# SX126xMB2xAS_e588v01a.net
KiCad netlist of a schematic drawn in Altium Designer
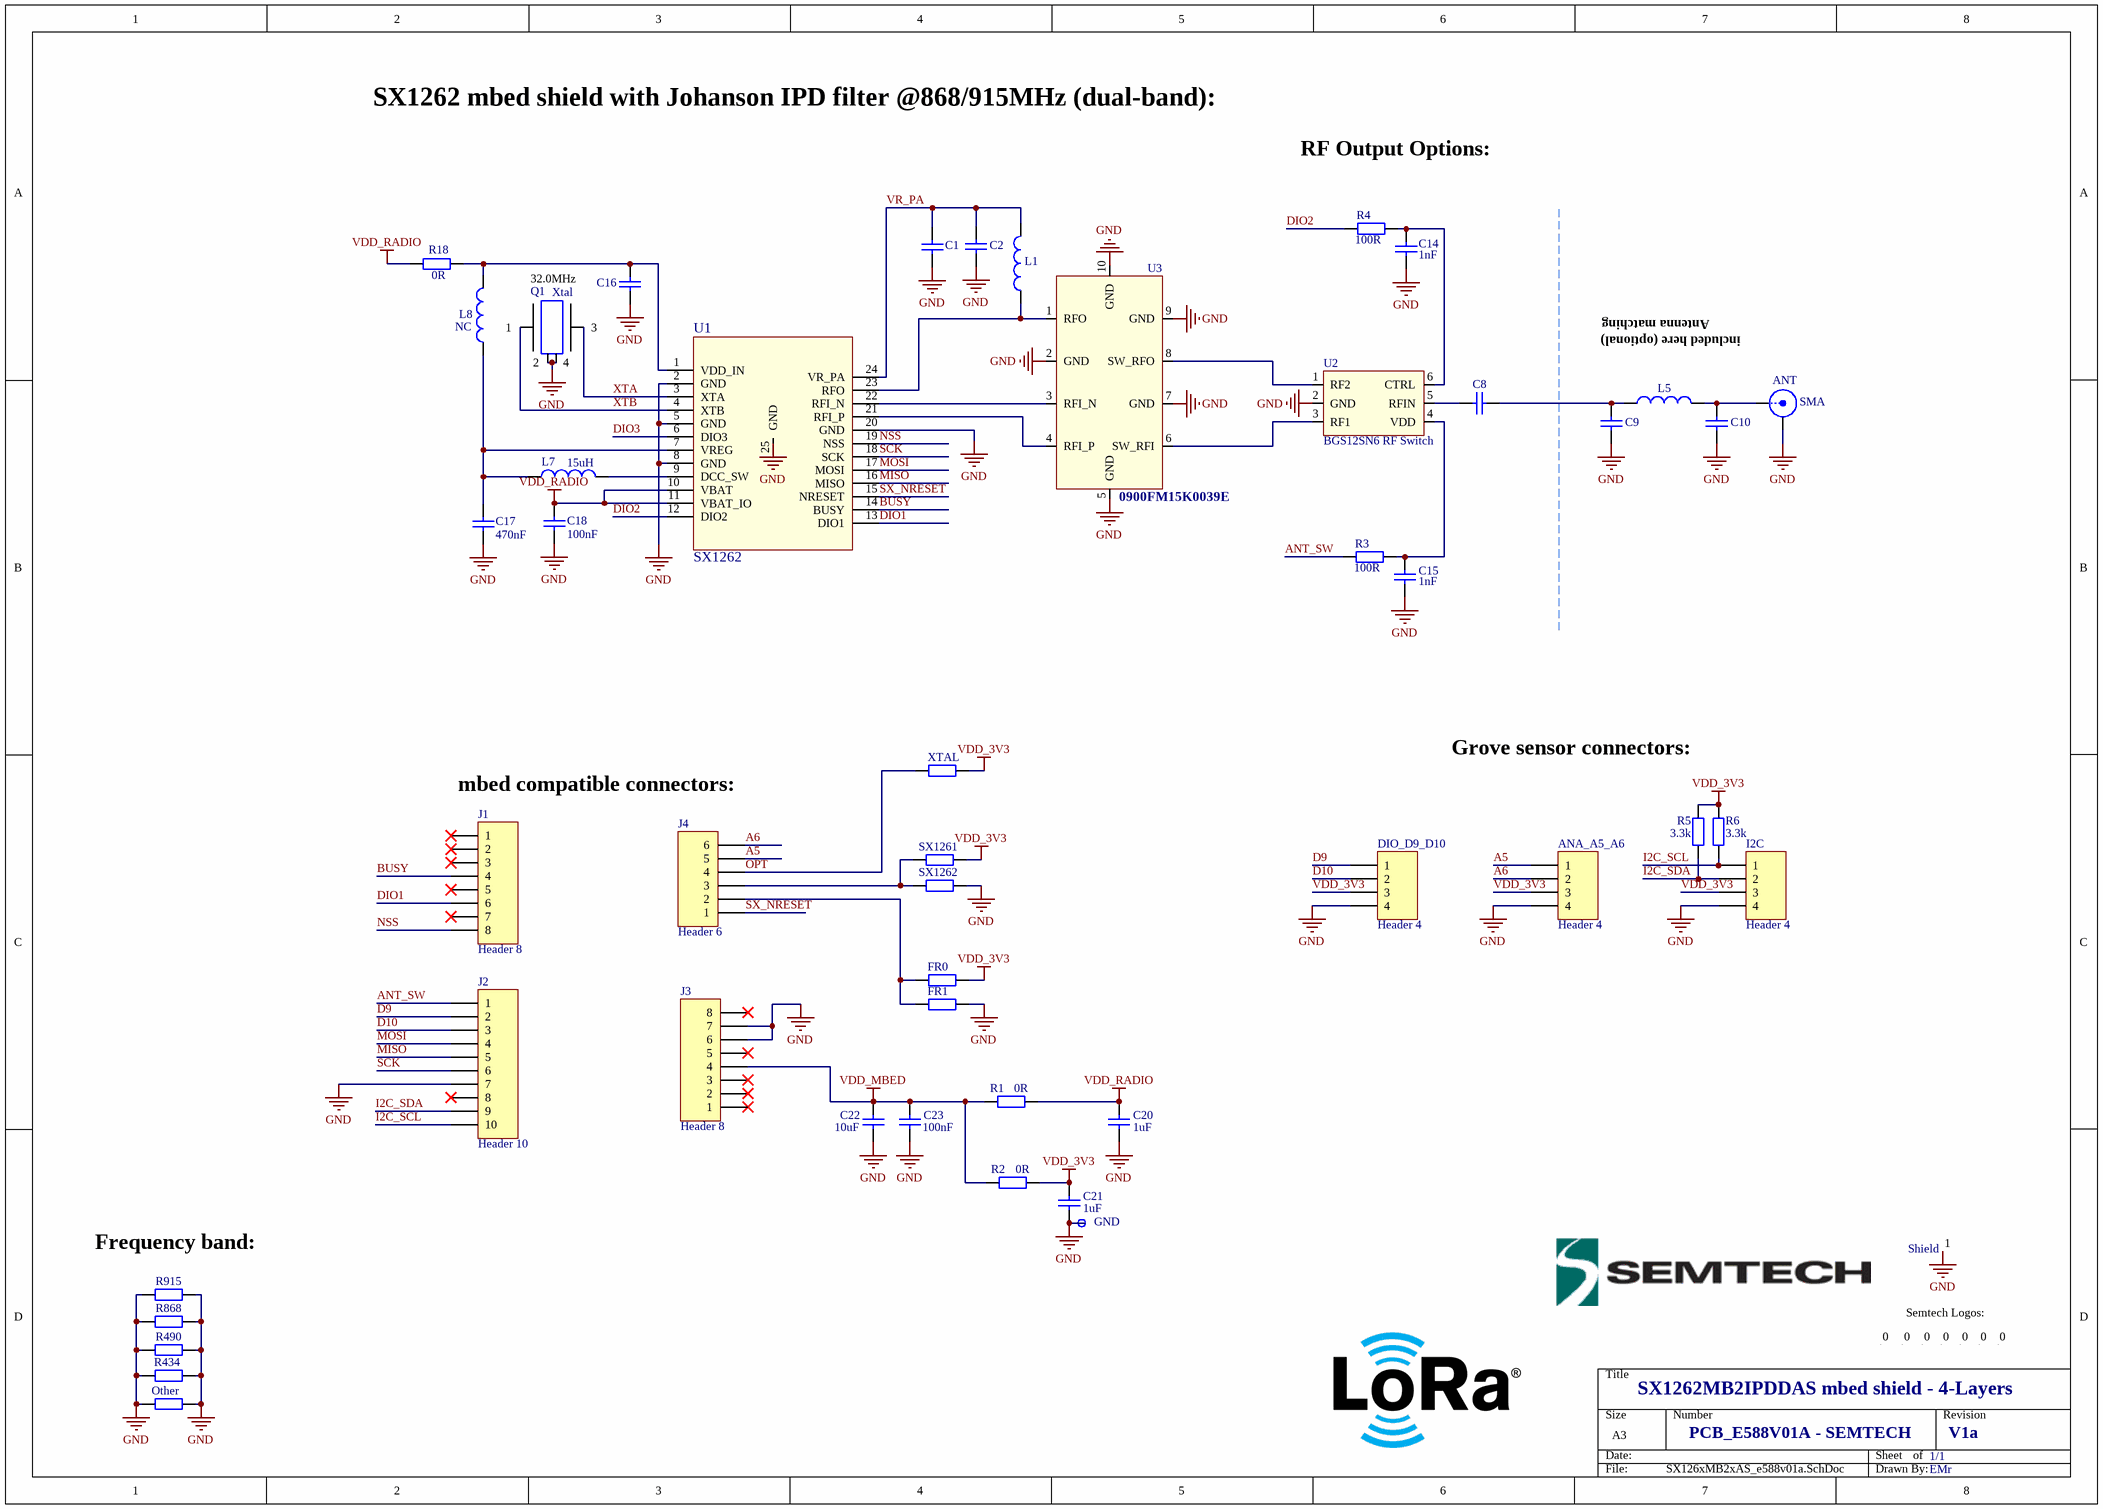
[diagram p0: SX126xMB2xAS_e588v01a.SchDoc]

(export (version "E")
  (design (tool "Eeschema 10.0.6"))
  (components
    (comp (ref "ANA_A5_A6")
      (value "Header 4")
      (footprint "1125S-4P_connector")
      (description "Header, 4-Pin")
      (fields (field (name "PUBLISHER") "Altium Limited"))
      (libsource (lib "SX126xMB2xAS_e588v01a") (part "Header 4"))
    )
    (comp (ref "ANT")
      (value "SMA")
      (footprint "SMA_end_launch_1.0mm_9.52mm")
      (description "SMA Straight Connector")
      (fields (field (name "PUBLISHER") "Altium Limited"))
      (libsource (lib "SX126xMB2xAS_e588v01a") (part "SMA"))
    )
    (comp (ref "C1")
      (value "Cap")
      (footprint "rlc_201_smd")
      (description "Capacitor SMD")
      (fields (field (name "PUBLISHER") "Altium Limited"))
      (libsource (lib "SX126xMB2xAS_e588v01a") (part "Cap"))
    )
    (comp (ref "C2")
      (value "Cap")
      (footprint "rlc_201_smd")
      (description "Capacitor SMD")
      (fields (field (name "PUBLISHER") "Altium Limited"))
      (libsource (lib "SX126xMB2xAS_e588v01a") (part "Cap"))
    )
    (comp (ref "C8")
      (value "Cap")
      (footprint "rlc_201_smd")
      (description "Capacitor SMD")
      (fields (field (name "PUBLISHER") "Altium Limited"))
      (libsource (lib "SX126xMB2xAS_e588v01a") (part "Cap"))
    )
    (comp (ref "C9")
      (value "Cap")
      (footprint "rlc_201_smd")
      (description "Capacitor SMD")
      (fields (field (name "PUBLISHER") "Altium Limited"))
      (libsource (lib "SX126xMB2xAS_e588v01a") (part "Cap"))
    )
    (comp (ref "C10")
      (value "Cap")
      (footprint "rlc_201_smd")
      (description "Capacitor SMD")
      (fields (field (name "PUBLISHER") "Altium Limited"))
      (libsource (lib "SX126xMB2xAS_e588v01a") (part "Cap"))
    )
    (comp (ref "C14")
      (value "1nF")
      (footprint "rlc_201_smd")
      (description "Capacitor SMD")
      (fields (field (name "Comment") "Cap") (field (name "PUBLISHER") "Altium Limited"))
      (libsource (lib "SX126xMB2xAS_e588v01a") (part "Cap"))
    )
    (comp (ref "C15")
      (value "1nF")
      (footprint "rlc_201_smd")
      (description "Capacitor SMD")
      (fields (field (name "Comment") "Cap") (field (name "PUBLISHER") "Altium Limited"))
      (libsource (lib "SX126xMB2xAS_e588v01a") (part "Cap"))
    )
    (comp (ref "C16")
      (value "Cap")
      (footprint "rlc_402_smd_small")
      (description "Capacitor SMD")
      (fields (field (name "PUBLISHER") "Altium Limited"))
      (libsource (lib "SX126xMB2xAS_e588v01a") (part "Cap"))
    )
    (comp (ref "C17")
      (value "470nF")
      (footprint "rlc_402_smd_small")
      (description "Capacitor SMD")
      (fields (field (name "Comment") "Cap") (field (name "PUBLISHER") "Altium Limited"))
      (libsource (lib "SX126xMB2xAS_e588v01a") (part "Cap"))
    )
    (comp (ref "C18")
      (value "100nF")
      (footprint "rlc_201_smd")
      (description "Capacitor SMD")
      (fields (field (name "Comment") "Cap") (field (name "PUBLISHER") "Altium Limited"))
      (libsource (lib "SX126xMB2xAS_e588v01a") (part "Cap"))
    )
    (comp (ref "C20")
      (value "1uF")
      (footprint "rlc_603_smd")
      (description "Capacitor SMD")
      (fields (field (name "Comment") "Cap") (field (name "PUBLISHER") "Altium Limited"))
      (libsource (lib "SX126xMB2xAS_e588v01a") (part "Cap"))
    )
    (comp (ref "C21")
      (value "1uF")
      (footprint "rlc_603_smd")
      (description "Capacitor SMD")
      (fields (field (name "Comment") "Cap") (field (name "PUBLISHER") "Altium Limited"))
      (libsource (lib "SX126xMB2xAS_e588v01a") (part "Cap"))
    )
    (comp (ref "C22")
      (value "10uF")
      (footprint "rlc_603_smd")
      (description "Capacitor SMD")
      (fields (field (name "Comment") "Cap") (field (name "PUBLISHER") "Altium Limited"))
      (libsource (lib "SX126xMB2xAS_e588v01a") (part "Cap"))
    )
    (comp (ref "C23")
      (value "100nF")
      (footprint "rlc_201_smd")
      (description "Capacitor SMD")
      (fields (field (name "Comment") "Cap") (field (name "PUBLISHER") "Altium Limited"))
      (libsource (lib "SX126xMB2xAS_e588v01a") (part "Cap"))
    )
    (comp (ref "DIO_D9_D10")
      (value "Header 4")
      (footprint "1125S-4P_connector")
      (description "Header, 4-Pin")
      (fields (field (name "PUBLISHER") "Altium Limited"))
      (libsource (lib "SX126xMB2xAS_e588v01a") (part "Header 4"))
    )
    (comp (ref "FR0")
      (value "Resistor")
      (footprint "rlc_402_smd")
      (description "Resistor SMD - IEC symbol version")
      (libsource (lib "") (part "Resistor_2"))
    )
    (comp (ref "FR1")
      (value "Resistor")
      (footprint "rlc_402_smd")
      (description "Resistor SMD - IEC symbol version")
      (libsource (lib "") (part "Resistor_2"))
    )
    (comp (ref "GND")
      (value "Test Pin")
      (footprint "pin_0.9mm")
      (libsource (lib "SX126xMB2xAS_e588v01a") (part "test_pin"))
    )
    (comp (ref "I2C")
      (value "Header 4")
      (footprint "1125S-4P_connector")
      (description "Header, 4-Pin")
      (fields (field (name "PUBLISHER") "Altium Limited"))
      (libsource (lib "SX126xMB2xAS_e588v01a") (part "Header 4"))
    )
    (comp (ref "J1")
      (value "Header 8")
      (footprint "HDR1X8")
      (description "Header, 8-Pin")
      (fields (field (name "PUBLISHER") "Altium Limited"))
      (libsource (lib "SX126xMB2xAS_e588v01a") (part "Header 8"))
    )
    (comp (ref "J2")
      (value "Header 10")
      (footprint "HDR1X10")
      (description "Header, 10-Pin")
      (fields (field (name "PUBLISHER") "Altium Limited"))
      (libsource (lib "SX126xMB2xAS_e588v01a") (part "Header 10"))
    )
    (comp (ref "J3")
      (value "Header 8")
      (footprint "HDR1X8")
      (description "Header, 8-Pin")
      (fields (field (name "PUBLISHER") "Altium Limited"))
      (libsource (lib "") (part "Header 8_1"))
    )
    (comp (ref "J4")
      (value "Header 6")
      (footprint "HDR1X6")
      (description "Header, 6-Pin")
      (fields (field (name "PUBLISHER") "Altium Limited"))
      (libsource (lib "SX126xMB2xAS_e588v01a") (part "Header 6"))
    )
    (comp (ref "L1")
      (value "Inductor")
      (footprint "rlc_402_smd_small")
      (description "Inductor SMD")
      (fields (field (name "PUBLISHER") "Altium Limited"))
      (libsource (lib "SX126xMB2xAS_e588v01a") (part "Inductor"))
    )
    (comp (ref "L5")
      (value "Inductor")
      (footprint "rlc_201_smd")
      (description "Inductor SMD")
      (fields (field (name "PUBLISHER") "Altium Limited"))
      (libsource (lib "SX126xMB2xAS_e588v01a") (part "Inductor"))
    )
    (comp (ref "L7")
      (value "15uH")
      (footprint "rlc_805_smd_small")
      (description "Inductor SMD")
      (fields (field (name "Comment") "Inductor") (field (name "PUBLISHER") "Altium Limited"))
      (libsource (lib "SX126xMB2xAS_e588v01a") (part "Inductor"))
    )
    (comp (ref "L8")
      (value "NC")
      (footprint "rlc_402_smd_small")
      (description "Inductor SMD")
      (fields (field (name "Comment") "Inductor") (field (name "PUBLISHER") "Altium Limited"))
      (libsource (lib "") (part "Inductor_1"))
    )
    (comp (ref "Logo Bot1")
      (value "Logo symbol")
      (footprint "Logo LoRa Size4")
      (description "Schematic symbol for Logo")
      (libsource (lib "SX126xMB2xAS_e588v01a") (part "Logo"))
    )
    (comp (ref "Logo ESD1")
      (value "Logo symbol")
      (footprint "Logo ESD")
      (description "Schematic symbol for Logo")
      (libsource (lib "SX126xMB2xAS_e588v01a") (part "Logo"))
    )
    (comp (ref "Logo Recycling1")
      (value "Logo symbol")
      (footprint "Logo Recycling1")
      (description "Schematic symbol for Logo")
      (libsource (lib "SX126xMB2xAS_e588v01a") (part "Logo"))
    )
    (comp (ref "Logo Semtech_1")
      (value "Logo symbol")
      (footprint "logo_semtech_horiz_size3")
      (description "Schematic symbol for Logo")
      (libsource (lib "SX126xMB2xAS_e588v01a") (part "Logo"))
    )
    (comp (ref "Logo_LoRA_Top1")
      (value "Logo symbol")
      (footprint "Logo LoRa Size4")
      (description "Schematic symbol for Logo")
      (libsource (lib "SX126xMB2xAS_e588v01a") (part "Logo"))
    )
    (comp (ref "Logo_mbed1")
      (value "Logo symbol")
      (footprint "logo mbed 2")
      (description "Schematic symbol for Logo")
      (libsource (lib "SX126xMB2xAS_e588v01a") (part "Logo"))
    )
    (comp (ref "Logo_Semtech1")
      (value "Logo symbol")
      (footprint "logo_semtech_horiz_size4")
      (description "Schematic symbol for Logo")
      (libsource (lib "SX126xMB2xAS_e588v01a") (part "Logo"))
    )
    (comp (ref "Other")
      (value "Resistor")
      (footprint "rlc_402_smd")
      (description "Resistor SMD - IEC symbol version")
      (libsource (lib "SX126xMB2xAS_e588v01a") (part "Resistor"))
    )
    (comp (ref "Q1")
      (value "Xtal")
      (footprint "nd2016da")
      (description "Crystal with GND pins")
      (fields (field (name "ALTIUM_VALUE") "32.0MHz"))
      (libsource (lib "SX126xMB2xAS_e588v01a") (part "Xtal GND"))
    )
    (comp (ref "R1")
      (value "0R")
      (footprint "rlc_603_smd")
      (description "Resistor SMD - IEC symbol version")
      (fields (field (name "Comment") "Resistor"))
      (libsource (lib "SX126xMB2xAS_e588v01a") (part "Resistor"))
    )
    (comp (ref "R2")
      (value "0R")
      (footprint "rlc_603_smd")
      (description "Resistor SMD - IEC symbol version")
      (fields (field (name "Comment") "Resistor"))
      (libsource (lib "SX126xMB2xAS_e588v01a") (part "Resistor"))
    )
    (comp (ref "R3")
      (value "100R")
      (footprint "rlc_201_smd")
      (description "Resistor SMD - IEC symbol version")
      (fields (field (name "Comment") "Resistor"))
      (libsource (lib "SX126xMB2xAS_e588v01a") (part "Resistor"))
    )
    (comp (ref "R4")
      (value "100R")
      (footprint "rlc_201_smd")
      (description "Resistor SMD - IEC symbol version")
      (fields (field (name "Comment") "Resistor"))
      (libsource (lib "SX126xMB2xAS_e588v01a") (part "Resistor"))
    )
    (comp (ref "R5")
      (value "3.3k")
      (footprint "rlc_201_smd")
      (description "Resistor SMD - IEC symbol version")
      (fields (field (name "Comment") "Resistor"))
      (libsource (lib "") (part "Resistor_1"))
    )
    (comp (ref "R6")
      (value "3.3k")
      (footprint "rlc_201_smd")
      (description "Resistor SMD - IEC symbol version")
      (fields (field (name "Comment") "Resistor"))
      (libsource (lib "") (part "Resistor_1"))
    )
    (comp (ref "R18")
      (value "0R")
      (footprint "rlc_402_smd_small")
      (description "Resistor SMD - IEC symbol version")
      (fields (field (name "Comment") "Resistor"))
      (libsource (lib "SX126xMB2xAS_e588v01a") (part "Resistor"))
    )
    (comp (ref "R434")
      (value "Resistor")
      (footprint "rlc_402_smd")
      (description "Resistor SMD - IEC symbol version")
      (libsource (lib "SX126xMB2xAS_e588v01a") (part "Resistor"))
    )
    (comp (ref "R490")
      (value "Resistor")
      (footprint "rlc_402_smd")
      (description "Resistor SMD - IEC symbol version")
      (libsource (lib "SX126xMB2xAS_e588v01a") (part "Resistor"))
    )
    (comp (ref "R868")
      (value "Resistor")
      (footprint "rlc_402_smd")
      (description "Resistor SMD - IEC symbol version")
      (libsource (lib "SX126xMB2xAS_e588v01a") (part "Resistor"))
    )
    (comp (ref "R915")
      (value "Resistor")
      (footprint "rlc_402_smd")
      (description "Resistor SMD - IEC symbol version")
      (libsource (lib "SX126xMB2xAS_e588v01a") (part "Resistor"))
    )
    (comp (ref "Shield")
      (value "Logo symbol")
      (footprint "BMIS-209-F - Shield")
      (description "Shield - EMI Gasket - Standard Surface Mount Shields")
      (libsource (lib "SX126xMB2xAS_e588v01a") (part "Shield"))
    )
    (comp (ref "SX1261")
      (value "Resistor")
      (footprint "rlc_402_smd")
      (description "Resistor SMD - IEC symbol version")
      (libsource (lib "") (part "Resistor_2"))
    )
    (comp (ref "SX1262")
      (value "Resistor")
      (footprint "rlc_402_smd")
      (description "Resistor SMD - IEC symbol version")
      (libsource (lib "") (part "Resistor_2"))
    )
    (comp (ref "U1")
      (value "SX1262")
      (footprint "vqfn24_4x4mm")
      (description "SX1262- Ultra low power RF transceiver")
      (libsource (lib "SX126xMB2xAS_e588v01a") (part "SX126x"))
    )
    (comp (ref "U2")
      (value "BGS12SN6 RF Switch")
      (footprint "TSNP-6-2")
      (description "BGS12SN6 Infineon RF Switch")
      (libsource (lib "SX126xMB2xAS_e588v01a") (part "BGS12SN6 RF Switch"))
    )
    (comp (ref "U3")
      (value "0900FM15K0039E")
      (footprint "IPD Filter")
      (description "0900FM15D0039 - Johanson IPD Filter for SX1261, SX1262")
      (libsource (lib "SX126xMB2xAS_e588v01a") (part "IPD filter"))
    )
    (comp (ref "XTAL")
      (value "Resistor")
      (footprint "rlc_402_smd")
      (description "Resistor SMD - IEC symbol version")
      (libsource (lib "") (part "Resistor_2"))
    )
  )
  (nets
    (net (code "1") (name "/A5") (class "Default")
      (node (ref "ANA_A5_A6") (pin "1") (pinfunction "1_1") (pintype "passive"))
      (node (ref "J4") (pin "5") (pinfunction "5_5") (pintype "passive"))
    )
    (net (code "2") (name "/A6") (class "Default")
      (node (ref "ANA_A5_A6") (pin "2") (pinfunction "2_2") (pintype "passive"))
      (node (ref "J4") (pin "6") (pinfunction "6_6") (pintype "passive"))
    )
    (net (code "3") (name "/ANT_SW") (class "Default")
      (node (ref "J2") (pin "1") (pinfunction "1_1") (pintype "passive"))
      (node (ref "R3") (pin "2") (pinfunction "2_2") (pintype "passive"))
    )
    (net (code "4") (name "/BUSY") (class "Default")
      (node (ref "J1") (pin "4") (pinfunction "4_4") (pintype "passive"))
      (node (ref "U1") (pin "14") (pinfunction "BUSY_14") (pintype "passive"))
    )
    (net (code "5") (name "/D9") (class "Default")
      (node (ref "DIO_D9_D10") (pin "1") (pinfunction "1_1") (pintype "passive"))
      (node (ref "J2") (pin "2") (pinfunction "2_2") (pintype "passive"))
    )
    (net (code "6") (name "/D10") (class "Default")
      (node (ref "DIO_D9_D10") (pin "2") (pinfunction "2_2") (pintype "passive"))
      (node (ref "J2") (pin "3") (pinfunction "3_3") (pintype "passive"))
    )
    (net (code "7") (name "/DIO1") (class "Default")
      (node (ref "J1") (pin "6") (pinfunction "6_6") (pintype "passive"))
      (node (ref "U1") (pin "13") (pinfunction "DIO1_13") (pintype "passive"))
    )
    (net (code "8") (name "/DIO2") (class "Default")
      (node (ref "R4") (pin "2") (pinfunction "2_2") (pintype "passive"))
      (node (ref "U1") (pin "12") (pinfunction "DIO2_12") (pintype "passive"))
    )
    (net (code "9") (name "/DIO3") (class "Default")
      (node (ref "U1") (pin "6") (pinfunction "DIO3_6") (pintype "passive"))
    )
    (net (code "10") (name "/I2C_SCL") (class "Default")
      (node (ref "I2C") (pin "1") (pinfunction "1_1") (pintype "passive"))
      (node (ref "J2") (pin "10") (pinfunction "10_10") (pintype "passive"))
      (node (ref "R6") (pin "1") (pinfunction "1_1") (pintype "passive"))
    )
    (net (code "11") (name "/I2C_SDA") (class "Default")
      (node (ref "I2C") (pin "2") (pinfunction "2_2") (pintype "passive"))
      (node (ref "J2") (pin "9") (pinfunction "9_9") (pintype "passive"))
      (node (ref "R5") (pin "1") (pinfunction "1_1") (pintype "passive"))
    )
    (net (code "12") (name "/MISO") (class "Default")
      (node (ref "J2") (pin "5") (pinfunction "5_5") (pintype "passive"))
      (node (ref "U1") (pin "16") (pinfunction "MISO_16") (pintype "passive"))
    )
    (net (code "13") (name "/MOSI") (class "Default")
      (node (ref "J2") (pin "4") (pinfunction "4_4") (pintype "passive"))
      (node (ref "U1") (pin "17") (pinfunction "MOSI_17") (pintype "passive"))
    )
    (net (code "14") (name "/NSS") (class "Default")
      (node (ref "J1") (pin "8") (pinfunction "8_8") (pintype "passive"))
      (node (ref "U1") (pin "19") (pinfunction "NSS_19") (pintype "passive"))
    )
    (net (code "15") (name "/OPT") (class "Default")
      (node (ref "J4") (pin "4") (pinfunction "4_4") (pintype "passive"))
      (node (ref "XTAL") (pin "2") (pinfunction "2_2") (pintype "passive"))
    )
    (net (code "16") (name "/SCK") (class "Default")
      (node (ref "J2") (pin "6") (pinfunction "6_6") (pintype "passive"))
      (node (ref "U1") (pin "18") (pinfunction "SCK_18") (pintype "passive"))
    )
    (net (code "17") (name "/SX_NRESET") (class "Default")
      (node (ref "J4") (pin "1") (pinfunction "1_1") (pintype "passive"))
      (node (ref "U1") (pin "15") (pinfunction "NRESET_15") (pintype "passive"))
    )
    (net (code "18") (name "/VR_PA") (class "Default")
      (node (ref "C1") (pin "2") (pinfunction "2_2") (pintype "passive"))
      (node (ref "C2") (pin "2") (pinfunction "2_2") (pintype "passive"))
      (node (ref "L1") (pin "2") (pinfunction "2_2") (pintype "passive"))
      (node (ref "U1") (pin "24") (pinfunction "VR_PA_24") (pintype "power_in"))
    )
    (net (code "19") (name "/XTA") (class "Default")
      (node (ref "Q1") (pin "3") (pinfunction "3_3") (pintype "passive"))
      (node (ref "U1") (pin "3") (pinfunction "XTA_3") (pintype "passive"))
    )
    (net (code "20") (name "/XTB") (class "Default")
      (node (ref "Q1") (pin "1") (pinfunction "1_1") (pintype "passive"))
      (node (ref "U1") (pin "4") (pinfunction "XTB_4") (pintype "passive"))
    )
    (net (code "21") (name "GND") (class "Default")
      (node (ref "ANA_A5_A6") (pin "4") (pinfunction "4_4") (pintype "passive"))
      (node (ref "ANT") (pin "2") (pinfunction "GND_2") (pintype "passive"))
      (node (ref "C1") (pin "1") (pinfunction "1_1") (pintype "passive"))
      (node (ref "C10") (pin "1") (pinfunction "1_1") (pintype "passive"))
      (node (ref "C14") (pin "2") (pinfunction "2_2") (pintype "passive"))
      (node (ref "C15") (pin "2") (pinfunction "2_2") (pintype "passive"))
      (node (ref "C16") (pin "1") (pinfunction "1_1") (pintype "passive"))
      (node (ref "C17") (pin "1") (pinfunction "1_1") (pintype "passive"))
      (node (ref "C18") (pin "1") (pinfunction "1_1") (pintype "passive"))
      (node (ref "C2") (pin "1") (pinfunction "1_1") (pintype "passive"))
      (node (ref "C20") (pin "1") (pinfunction "1_1") (pintype "passive"))
      (node (ref "C21") (pin "1") (pinfunction "1_1") (pintype "passive"))
      (node (ref "C22") (pin "1") (pinfunction "1_1") (pintype "passive"))
      (node (ref "C23") (pin "1") (pinfunction "1_1") (pintype "passive"))
      (node (ref "C9") (pin "1") (pinfunction "1_1") (pintype "passive"))
      (node (ref "DIO_D9_D10") (pin "4") (pinfunction "4_4") (pintype "passive"))
      (node (ref "FR1") (pin "1") (pinfunction "1_1") (pintype "passive"))
      (node (ref "GND") (pin "1") (pinfunction "pin_1") (pintype "passive"))
      (node (ref "I2C") (pin "4") (pinfunction "4_4") (pintype "passive"))
      (node (ref "J2") (pin "7") (pinfunction "7_7") (pintype "passive"))
      (node (ref "J3") (pin "6") (pinfunction "6_6") (pintype "passive"))
      (node (ref "J3") (pin "7") (pinfunction "7_7") (pintype "passive"))
      (node (ref "Other") (pin "1") (pinfunction "1_1") (pintype "passive"))
      (node (ref "Other") (pin "2") (pinfunction "2_2") (pintype "passive"))
      (node (ref "Q1") (pin "2") (pinfunction "2_2") (pintype "passive"))
      (node (ref "Q1") (pin "4") (pinfunction "4_4") (pintype "passive"))
      (node (ref "R434") (pin "1") (pinfunction "1_1") (pintype "passive"))
      (node (ref "R434") (pin "2") (pinfunction "2_2") (pintype "passive"))
      (node (ref "R490") (pin "1") (pinfunction "1_1") (pintype "passive"))
      (node (ref "R490") (pin "2") (pinfunction "2_2") (pintype "passive"))
      (node (ref "R868") (pin "1") (pinfunction "1_1") (pintype "passive"))
      (node (ref "R868") (pin "2") (pinfunction "2_2") (pintype "passive"))
      (node (ref "R915") (pin "1") (pinfunction "1_1") (pintype "passive"))
      (node (ref "R915") (pin "2") (pinfunction "2_2") (pintype "passive"))
      (node (ref "SX1262") (pin "1") (pinfunction "1_1") (pintype "passive"))
      (node (ref "Shield") (pin "1") (pinfunction "1_1") (pintype "passive"))
      (node (ref "U1") (pin "2") (pinfunction "GND_2") (pintype "passive"))
      (node (ref "U1") (pin "20") (pinfunction "GND_20") (pintype "passive"))
      (node (ref "U1") (pin "25") (pinfunction "GND_25") (pintype "passive"))
      (node (ref "U1") (pin "5") (pinfunction "GND_5") (pintype "passive"))
      (node (ref "U1") (pin "8") (pinfunction "GND_8") (pintype "passive"))
      (node (ref "U2") (pin "2") (pinfunction "GND_2") (pintype "passive"))
      (node (ref "U3") (pin "10") (pinfunction "GND_10") (pintype "power_in"))
      (node (ref "U3") (pin "2") (pinfunction "GND_2") (pintype "power_in"))
      (node (ref "U3") (pin "5") (pinfunction "GND_5") (pintype "power_in"))
      (node (ref "U3") (pin "7") (pinfunction "GND_7") (pintype "power_in"))
      (node (ref "U3") (pin "9") (pinfunction "GND_9") (pintype "power_in"))
    )
    (net (code "22") (name "Net-(ANT-Signal)") (class "Default")
      (node (ref "ANT") (pin "1") (pinfunction "Signal_1") (pintype "passive"))
      (node (ref "C10") (pin "2") (pinfunction "2_2") (pintype "passive"))
      (node (ref "L5") (pin "2") (pinfunction "2_2") (pintype "passive"))
    )
    (net (code "23") (name "Net-(C8-Pad1)") (class "Default")
      (node (ref "C8") (pin "1") (pinfunction "1_1") (pintype "passive"))
      (node (ref "C9") (pin "2") (pinfunction "2_2") (pintype "passive"))
      (node (ref "L5") (pin "1") (pinfunction "1_1") (pintype "passive"))
    )
    (net (code "24") (name "Net-(FR0-Pad2)") (class "Default")
      (node (ref "FR0") (pin "2") (pinfunction "2_2") (pintype "passive"))
      (node (ref "FR1") (pin "2") (pinfunction "2_2") (pintype "passive"))
      (node (ref "J4") (pin "2") (pinfunction "2_2") (pintype "passive"))
    )
    (net (code "25") (name "Net-(J4-Pad3)") (class "Default")
      (node (ref "J4") (pin "3") (pinfunction "3_3") (pintype "passive"))
      (node (ref "SX1261") (pin "2") (pinfunction "2_2") (pintype "passive"))
      (node (ref "SX1262") (pin "2") (pinfunction "2_2") (pintype "passive"))
    )
    (net (code "26") (name "Net-(U1-DCC_SW)") (class "Default")
      (node (ref "L7") (pin "2") (pinfunction "2_2") (pintype "passive"))
      (node (ref "U1") (pin "9") (pinfunction "DCC_SW_9") (pintype "power_in"))
    )
    (net (code "27") (name "Net-(U1-RFI_N)") (class "Default")
      (node (ref "U1") (pin "22") (pinfunction "RFI_N_22") (pintype "passive"))
      (node (ref "U3") (pin "3") (pinfunction "RFI_N_3") (pintype "passive"))
    )
    (net (code "28") (name "Net-(U1-RFI_P)") (class "Default")
      (node (ref "U1") (pin "21") (pinfunction "RFI_P_21") (pintype "passive"))
      (node (ref "U3") (pin "4") (pinfunction "RFI_P_4") (pintype "passive"))
    )
    (net (code "29") (name "Net-(U1-RFO)") (class "Default")
      (node (ref "L1") (pin "1") (pinfunction "1_1") (pintype "passive"))
      (node (ref "U1") (pin "23") (pinfunction "RFO_23") (pintype "passive"))
      (node (ref "U3") (pin "1") (pinfunction "RFO_1") (pintype "passive"))
    )
    (net (code "30") (name "Net-(U1-VDD_IN)") (class "Default")
      (node (ref "C16") (pin "2") (pinfunction "2_2") (pintype "passive"))
      (node (ref "L8") (pin "1") (pinfunction "1_1") (pintype "passive"))
      (node (ref "R18") (pin "1") (pinfunction "1_1") (pintype "passive"))
      (node (ref "U1") (pin "1") (pinfunction "VDD_IN_1") (pintype "power_in"))
    )
    (net (code "31") (name "Net-(U1-VREG)") (class "Default")
      (node (ref "C17") (pin "2") (pinfunction "2_2") (pintype "passive"))
      (node (ref "L7") (pin "1") (pinfunction "1_1") (pintype "passive"))
      (node (ref "L8") (pin "2") (pinfunction "2_2") (pintype "passive"))
      (node (ref "U1") (pin "7") (pinfunction "VREG_7") (pintype "power_in"))
    )
    (net (code "32") (name "Net-(U2-CTRL)") (class "Default")
      (node (ref "C14") (pin "1") (pinfunction "1_1") (pintype "passive"))
      (node (ref "R4") (pin "1") (pinfunction "1_1") (pintype "passive"))
      (node (ref "U2") (pin "6") (pinfunction "CTRL_6") (pintype "passive"))
    )
    (net (code "33") (name "Net-(U2-RF1)") (class "Default")
      (node (ref "U2") (pin "3") (pinfunction "RF1_3") (pintype "passive"))
      (node (ref "U3") (pin "6") (pinfunction "SW_RFI_6") (pintype "passive"))
    )
    (net (code "34") (name "Net-(U2-RF2)") (class "Default")
      (node (ref "U2") (pin "1") (pinfunction "RF2_1") (pintype "passive"))
      (node (ref "U3") (pin "8") (pinfunction "SW_RFO_8") (pintype "passive"))
    )
    (net (code "35") (name "Net-(U2-RFIN)") (class "Default")
      (node (ref "C8") (pin "2") (pinfunction "2_2") (pintype "passive"))
      (node (ref "U2") (pin "5") (pinfunction "RFIN_5") (pintype "passive"))
    )
    (net (code "36") (name "Net-(U2-VDD)") (class "Default")
      (node (ref "C15") (pin "1") (pinfunction "1_1") (pintype "passive"))
      (node (ref "R3") (pin "1") (pinfunction "1_1") (pintype "passive"))
      (node (ref "U2") (pin "4") (pinfunction "VDD_4") (pintype "power_in"))
    )
    (net (code "37") (name "VDD_3V3") (class "Default")
      (node (ref "ANA_A5_A6") (pin "3") (pinfunction "3_3") (pintype "passive"))
      (node (ref "C21") (pin "2") (pinfunction "2_2") (pintype "passive"))
      (node (ref "DIO_D9_D10") (pin "3") (pinfunction "3_3") (pintype "passive"))
      (node (ref "FR0") (pin "1") (pinfunction "1_1") (pintype "passive"))
      (node (ref "I2C") (pin "3") (pinfunction "3_3") (pintype "passive"))
      (node (ref "R2") (pin "1") (pinfunction "1_1") (pintype "passive"))
      (node (ref "R5") (pin "2") (pinfunction "2_2") (pintype "passive"))
      (node (ref "R6") (pin "2") (pinfunction "2_2") (pintype "passive"))
      (node (ref "SX1261") (pin "1") (pinfunction "1_1") (pintype "passive"))
      (node (ref "XTAL") (pin "1") (pinfunction "1_1") (pintype "passive"))
    )
    (net (code "38") (name "VDD_MBED") (class "Default")
      (node (ref "C22") (pin "2") (pinfunction "2_2") (pintype "passive"))
      (node (ref "C23") (pin "2") (pinfunction "2_2") (pintype "passive"))
      (node (ref "J3") (pin "4") (pinfunction "4_4") (pintype "passive"))
      (node (ref "R1") (pin "2") (pinfunction "2_2") (pintype "passive"))
      (node (ref "R2") (pin "2") (pinfunction "2_2") (pintype "passive"))
    )
    (net (code "39") (name "VDD_RADIO") (class "Default")
      (node (ref "C18") (pin "2") (pinfunction "2_2") (pintype "passive"))
      (node (ref "C20") (pin "2") (pinfunction "2_2") (pintype "passive"))
      (node (ref "R1") (pin "1") (pinfunction "1_1") (pintype "passive"))
      (node (ref "R18") (pin "2") (pinfunction "2_2") (pintype "passive"))
      (node (ref "U1") (pin "10") (pinfunction "VBAT_10") (pintype "power_in"))
      (node (ref "U1") (pin "11") (pinfunction "VBAT_IO_11") (pintype "power_in"))
    )
    (net (code "40") (name "unconnected-(J1-Pad1)") (class "Default")
      (node (ref "J1") (pin "1") (pinfunction "1_1") (pintype "passive+no_connect"))
    )
    (net (code "41") (name "unconnected-(J1-Pad2)") (class "Default")
      (node (ref "J1") (pin "2") (pinfunction "2_2") (pintype "passive+no_connect"))
    )
    (net (code "42") (name "unconnected-(J1-Pad3)") (class "Default")
      (node (ref "J1") (pin "3") (pinfunction "3_3") (pintype "passive+no_connect"))
    )
    (net (code "43") (name "unconnected-(J1-Pad5)") (class "Default")
      (node (ref "J1") (pin "5") (pinfunction "5_5") (pintype "passive+no_connect"))
    )
    (net (code "44") (name "unconnected-(J1-Pad7)") (class "Default")
      (node (ref "J1") (pin "7") (pinfunction "7_7") (pintype "passive+no_connect"))
    )
    (net (code "45") (name "unconnected-(J2-Pad8)") (class "Default")
      (node (ref "J2") (pin "8") (pinfunction "8_8") (pintype "passive+no_connect"))
    )
    (net (code "46") (name "unconnected-(J3-Pad1)") (class "Default")
      (node (ref "J3") (pin "1") (pinfunction "1_1") (pintype "passive+no_connect"))
    )
    (net (code "47") (name "unconnected-(J3-Pad2)") (class "Default")
      (node (ref "J3") (pin "2") (pinfunction "2_2") (pintype "passive+no_connect"))
    )
    (net (code "48") (name "unconnected-(J3-Pad3)") (class "Default")
      (node (ref "J3") (pin "3") (pinfunction "3_3") (pintype "passive+no_connect"))
    )
    (net (code "49") (name "unconnected-(J3-Pad5)") (class "Default")
      (node (ref "J3") (pin "5") (pinfunction "5_5") (pintype "passive+no_connect"))
    )
    (net (code "50") (name "unconnected-(J3-Pad8)") (class "Default")
      (node (ref "J3") (pin "8") (pinfunction "8_8") (pintype "passive+no_connect"))
    )
    (net (code "51") (name "unconnected-(Logo Bot1-Pad0)") (class "Default")
      (node (ref "Logo Bot1") (pin "0") (pinfunction "0_0") (pintype "passive"))
    )
    (net (code "52") (name "unconnected-(Logo ESD1-Pad0)") (class "Default")
      (node (ref "Logo ESD1") (pin "0") (pinfunction "0_0") (pintype "passive"))
    )
    (net (code "53") (name "unconnected-(Logo Recycling1-Pad0)") (class "Default")
      (node (ref "Logo Recycling1") (pin "0") (pinfunction "0_0") (pintype "passive"))
    )
    (net (code "54") (name "unconnected-(Logo Semtech_1-Pad0)") (class "Default")
      (node (ref "Logo Semtech_1") (pin "0") (pinfunction "0_0") (pintype "passive"))
    )
    (net (code "55") (name "unconnected-(Logo_LoRA_Top1-Pad0)") (class "Default")
      (node (ref "Logo_LoRA_Top1") (pin "0") (pinfunction "0_0") (pintype "passive"))
    )
    (net (code "56") (name "unconnected-(Logo_Semtech1-Pad0)") (class "Default")
      (node (ref "Logo_Semtech1") (pin "0") (pinfunction "0_0") (pintype "passive"))
    )
    (net (code "57") (name "unconnected-(Logo_mbed1-Pad0)") (class "Default")
      (node (ref "Logo_mbed1") (pin "0") (pinfunction "0_0") (pintype "passive"))
    )
  )
)
